# quanton_rev_1.net
KiCad netlist of a schematic drawn in EAGLE
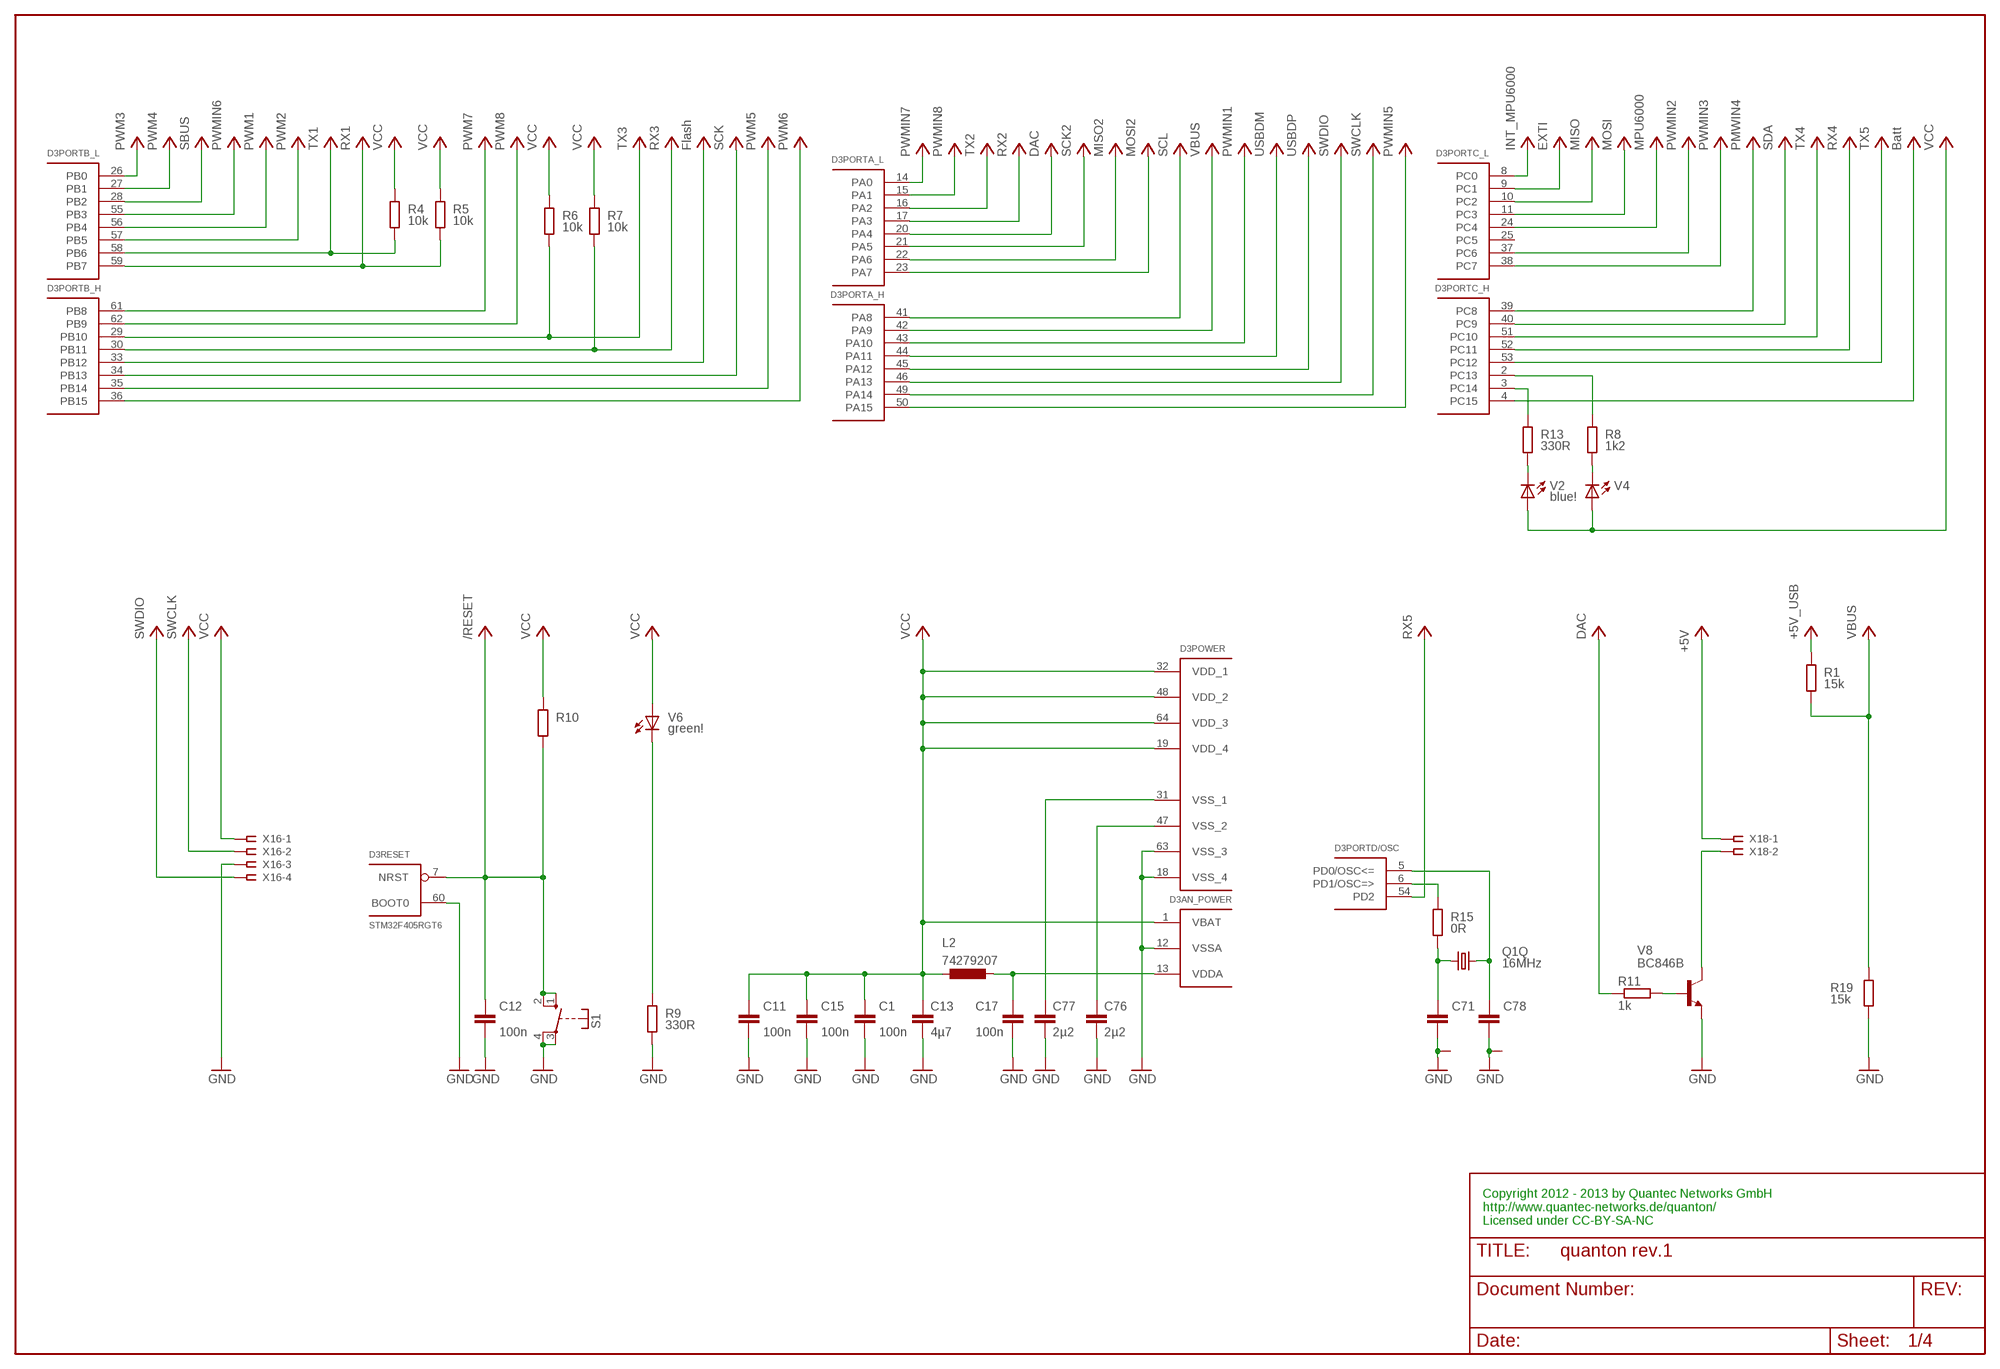
[diagram p0: schematic, sheet 1]
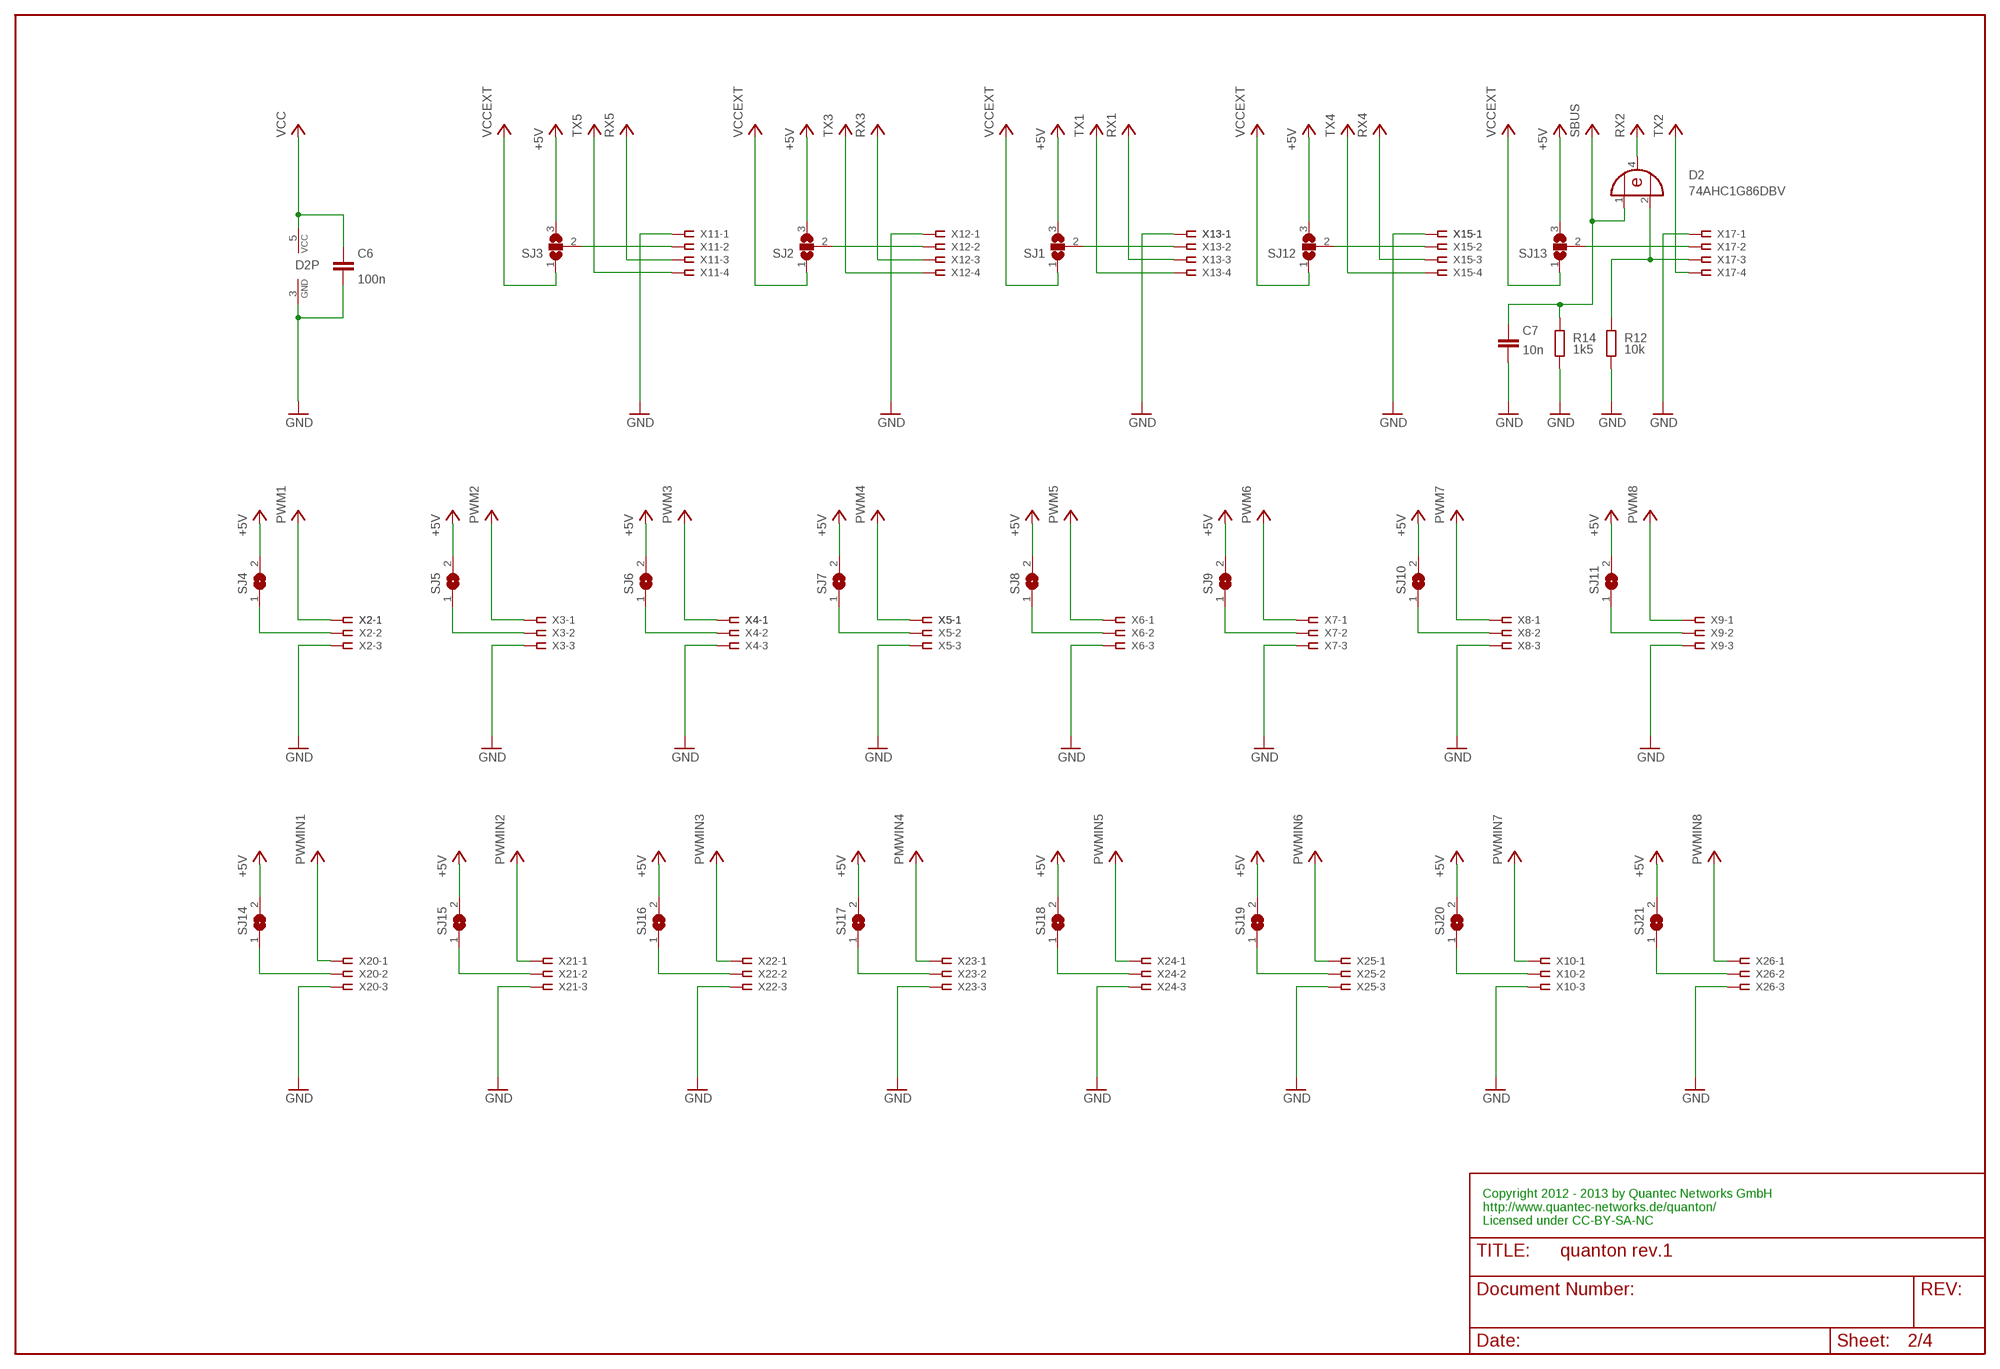
[diagram p1: schematic, sheet 2]
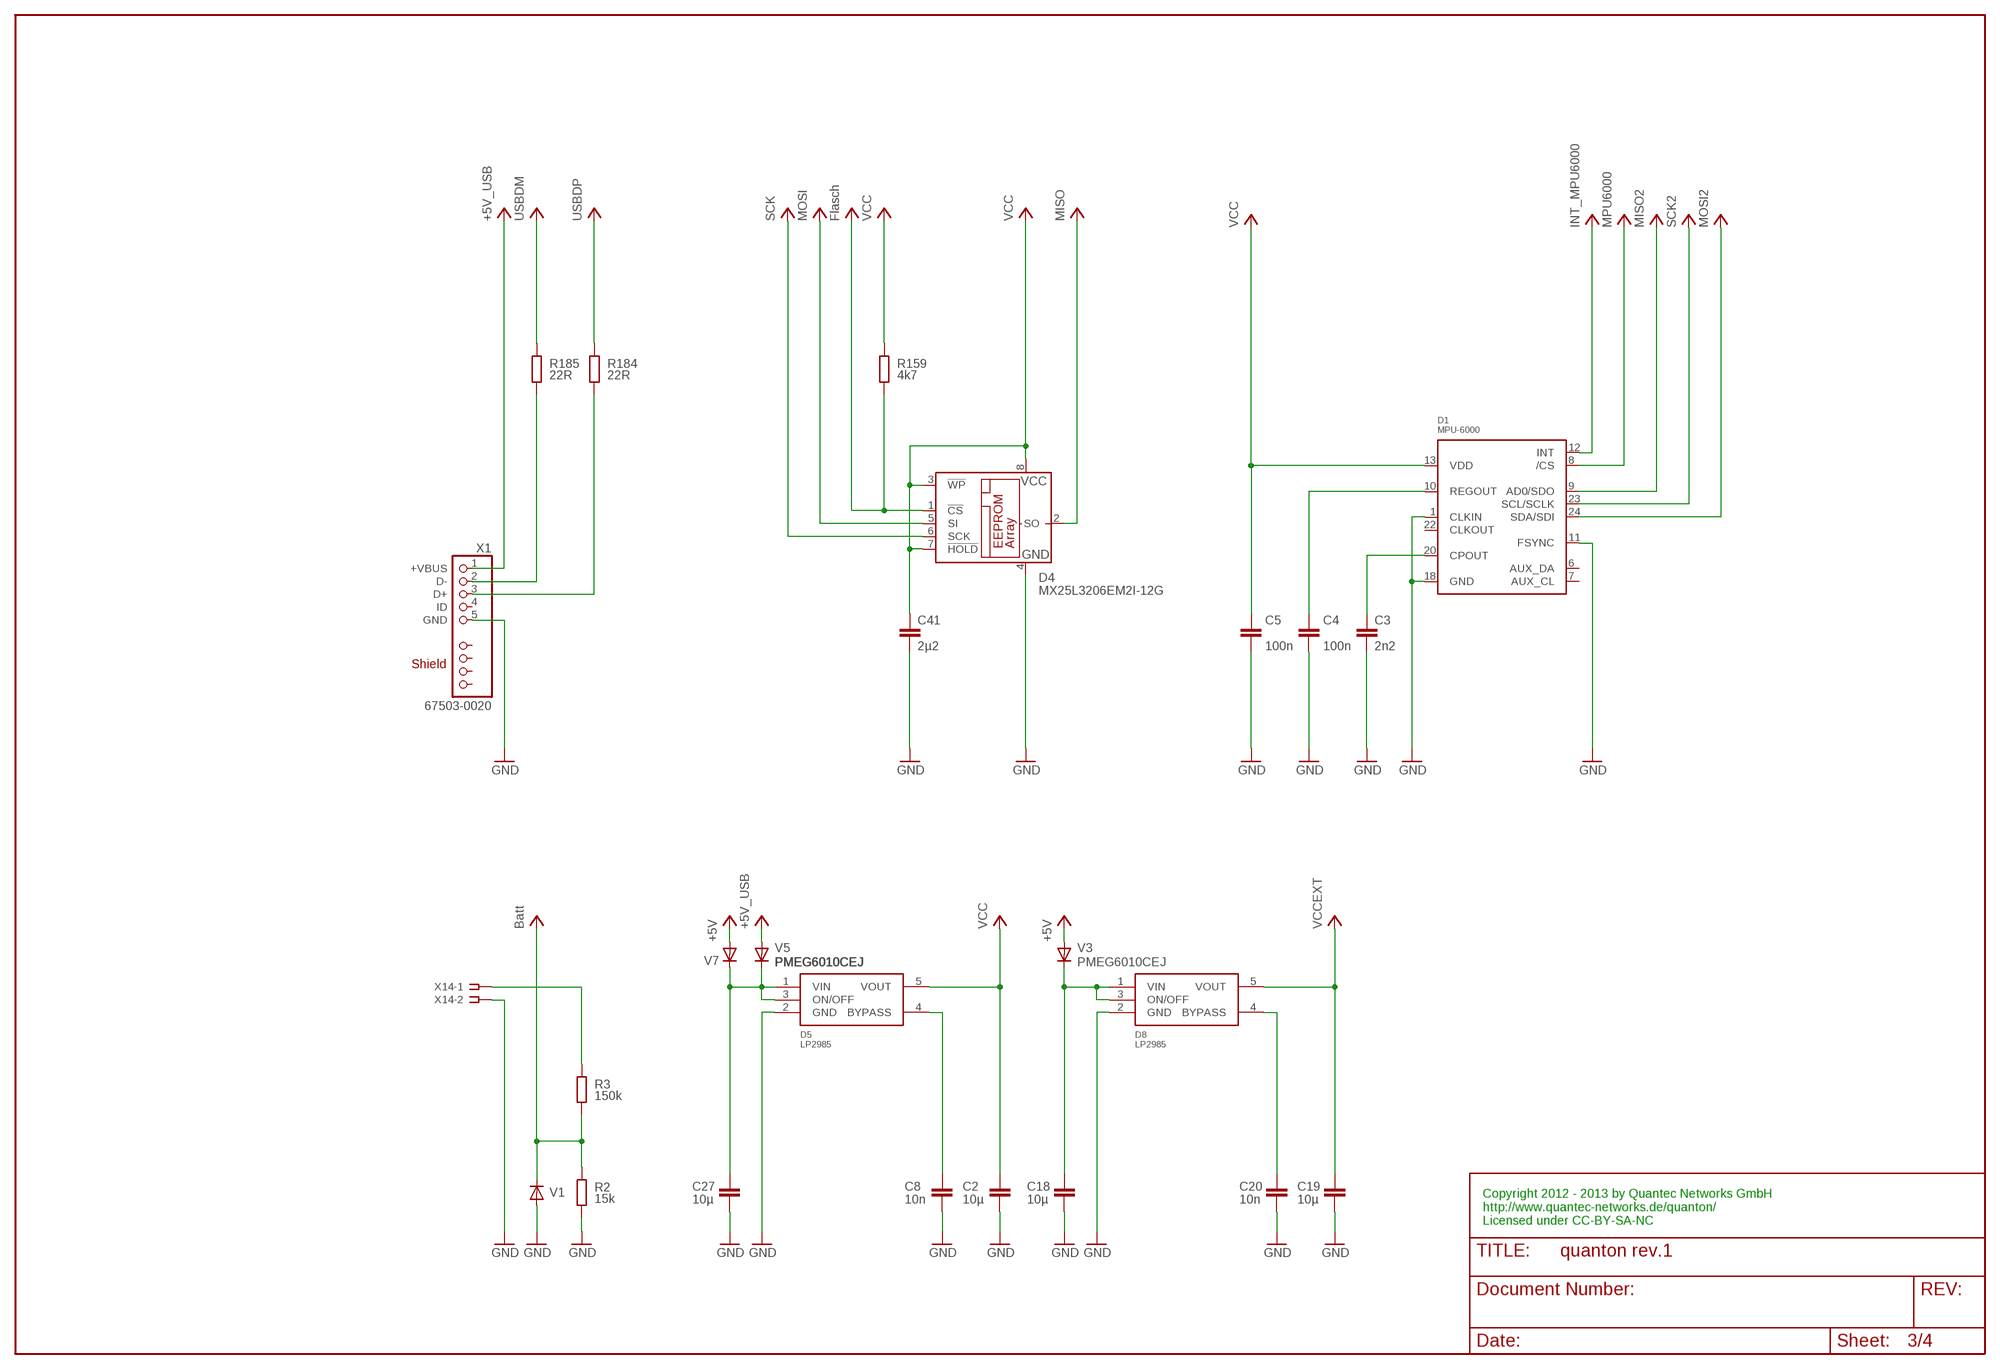
[diagram p2: schematic, sheet 3]
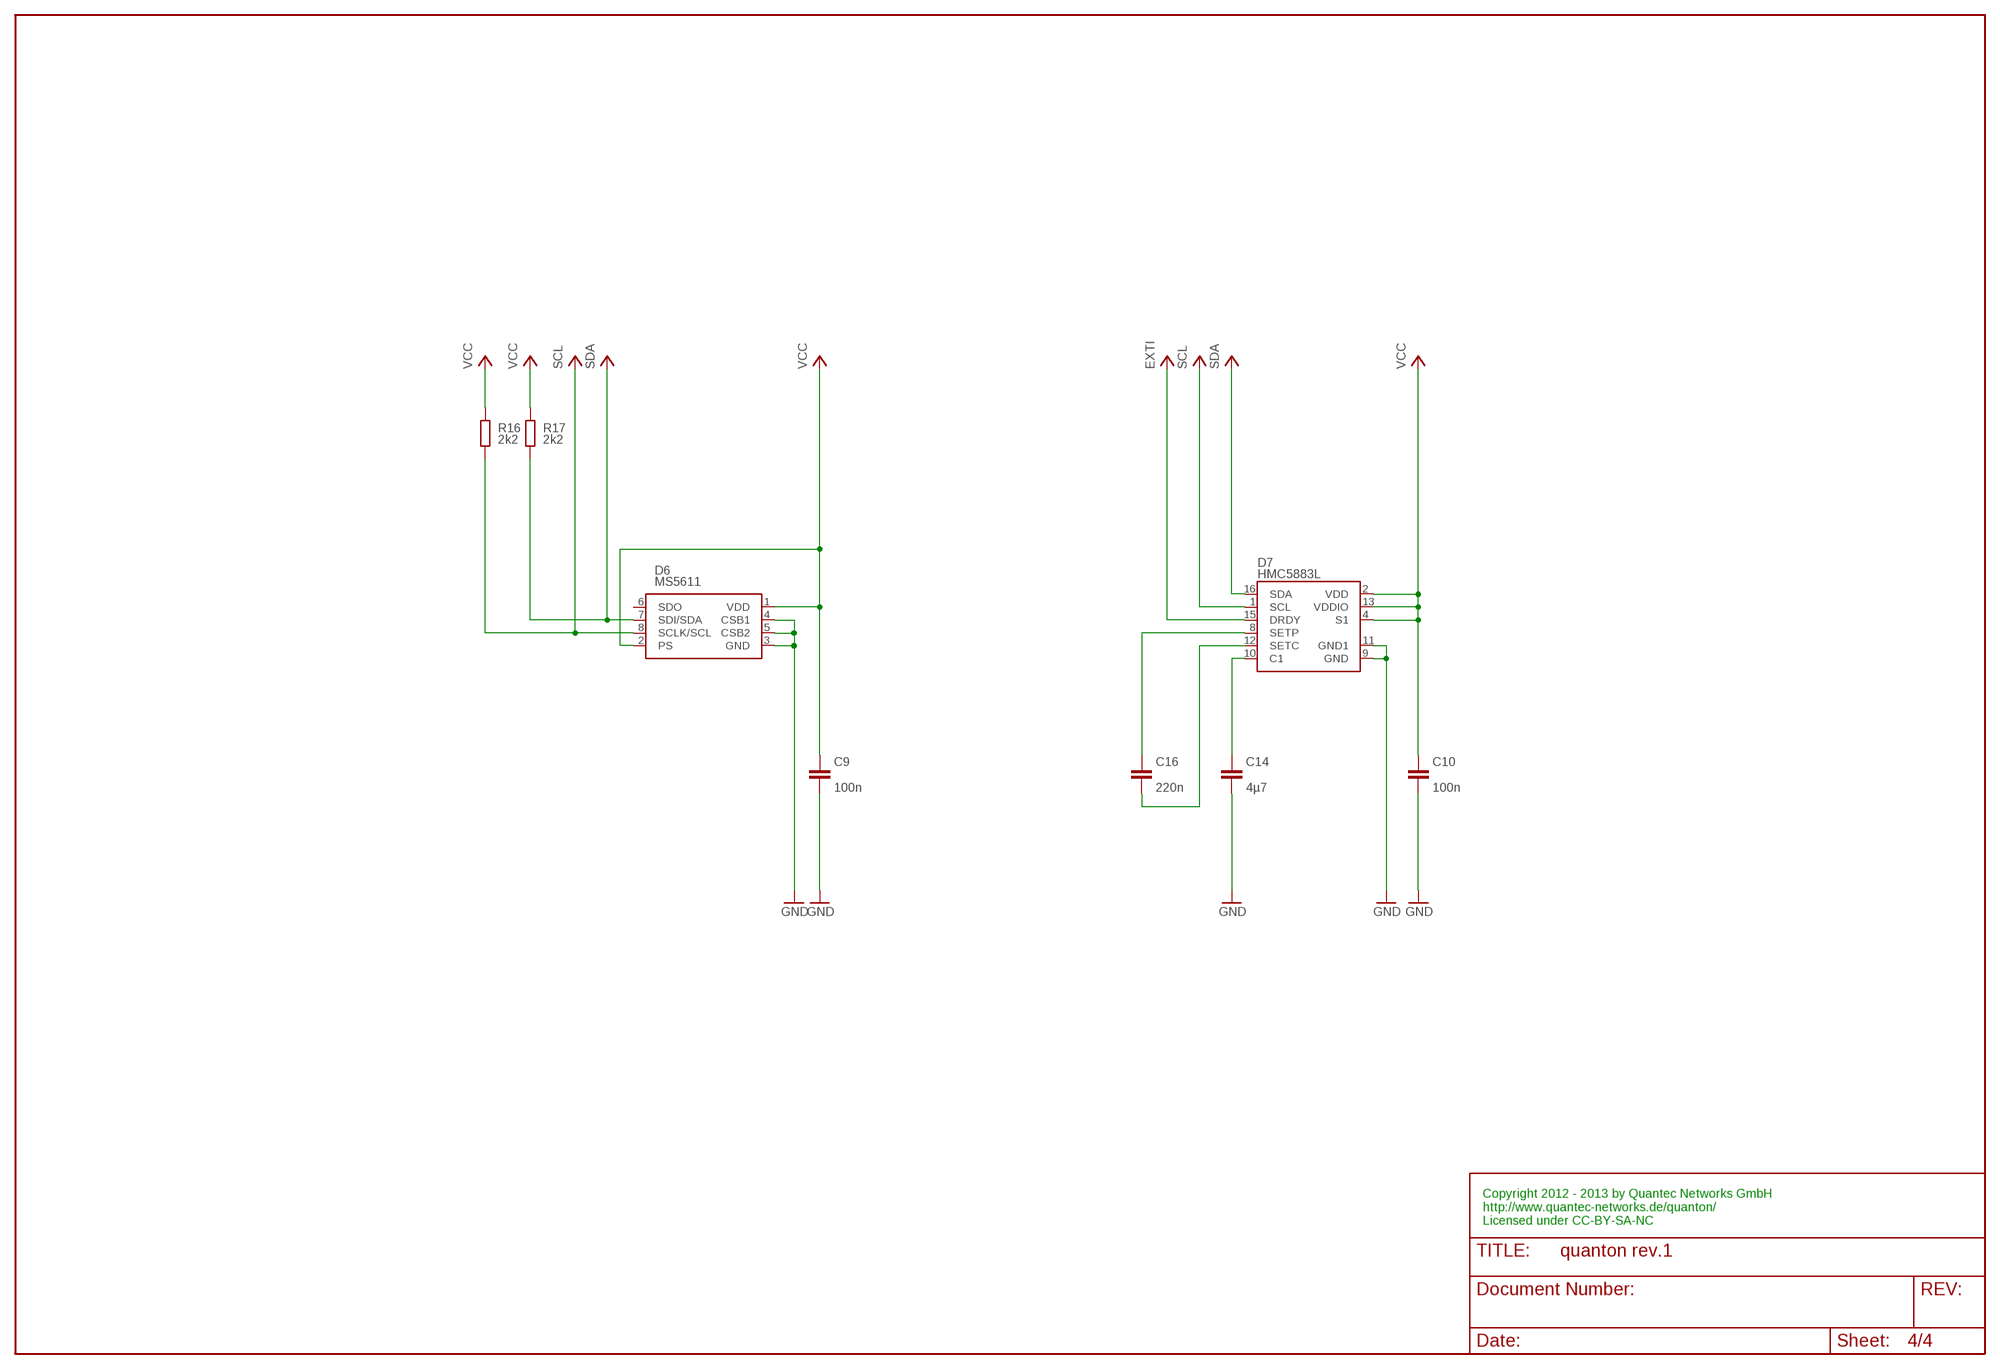
[diagram p3: schematic, sheet 4]

(export (version "E")
  (design (tool "Eeschema 10.0.6"))
  (components
    (comp (ref "C9")
      (value "100n")
      (footprint "eagle-import:C0402")
      (libsource (lib "eagle-import") (part "C-EUC0402"))
    )
    (comp (ref "C10")
      (value "100n")
      (footprint "eagle-import:C0402")
      (libsource (lib "eagle-import") (part "C-EUC0402"))
    )
    (comp (ref "C14")
      (value "4µ7")
      (footprint "eagle-import:C0805")
      (libsource (lib "eagle-import") (part "C-EUC0805"))
    )
    (comp (ref "C16")
      (value "220n")
      (footprint "eagle-import:C0603")
      (libsource (lib "eagle-import") (part "C-EUC0603"))
    )
    (comp (ref "D6")
      (value "MS5611")
      (footprint "eagle-import:QFN8-5X3")
      (libsource (lib "eagle-import") (part "MS5611"))
    )
    (comp (ref "D7")
      (value "HMC5883L")
      (footprint "eagle-import:LCC16-3X3")
      (libsource (lib "eagle-import") (part "HMC5883L"))
    )
    (comp (ref "R16")
      (value "2k2")
      (footprint "eagle-import:R0603")
      (libsource (lib "eagle-import") (part "R-EU_R0603"))
    )
    (comp (ref "R17")
      (value "2k2")
      (footprint "eagle-import:R0603")
      (libsource (lib "eagle-import") (part "R-EU_R0603"))
    )
    (comp (ref "C6")
      (value "100n")
      (footprint "eagle-import:C0402")
      (libsource (lib "eagle-import") (part "C-EUC0402"))
    )
    (comp (ref "C7")
      (value "10n")
      (footprint "eagle-import:C0603")
      (libsource (lib "eagle-import") (part "C-EUC0603"))
    )
    (comp (ref "D2")
      (value "74AHC1G86DBV")
      (footprint "eagle-import:SOT23-5")
      (fields (field (name "ABAS") "12532"))
      (libsource (lib "eagle-import") (part "741G86DBVAHC"))
    )
    (comp (ref "R12")
      (value "10k")
      (footprint "eagle-import:R0603")
      (libsource (lib "eagle-import") (part "R-EU_R0603"))
    )
    (comp (ref "R14")
      (value "1k5")
      (footprint "eagle-import:R0603")
      (libsource (lib "eagle-import") (part "R-EU_R0603"))
    )
    (comp (ref "SJ1")
      (value "SJ2W")
      (footprint "eagle-import:SJ_2")
      (libsource (lib "eagle-import") (part "SJ2W"))
    )
    (comp (ref "SJ2")
      (value "SJ2W")
      (footprint "eagle-import:SJ_2")
      (libsource (lib "eagle-import") (part "SJ2W"))
    )
    (comp (ref "SJ3")
      (value "SJ2W")
      (footprint "eagle-import:SJ_2")
      (libsource (lib "eagle-import") (part "SJ2W"))
    )
    (comp (ref "SJ4") (value "SJ") (footprint "eagle-import:SJ") (libsource (lib "eagle-import") (part "SJ")))
    (comp (ref "SJ5") (value "SJ") (footprint "eagle-import:SJ") (libsource (lib "eagle-import") (part "SJ")))
    (comp (ref "SJ6") (value "SJ") (footprint "eagle-import:SJ") (libsource (lib "eagle-import") (part "SJ")))
    (comp (ref "SJ7") (value "SJ") (footprint "eagle-import:SJ") (libsource (lib "eagle-import") (part "SJ")))
    (comp (ref "SJ8") (value "SJ") (footprint "eagle-import:SJ") (libsource (lib "eagle-import") (part "SJ")))
    (comp (ref "SJ9") (value "SJ") (footprint "eagle-import:SJ") (libsource (lib "eagle-import") (part "SJ")))
    (comp (ref "SJ10")
      (value "SJ")
      (footprint "eagle-import:SJ")
      (libsource (lib "eagle-import") (part "SJ"))
    )
    (comp (ref "SJ11")
      (value "SJ")
      (footprint "eagle-import:SJ")
      (libsource (lib "eagle-import") (part "SJ"))
    )
    (comp (ref "SJ12")
      (value "SJ2W")
      (footprint "eagle-import:SJ_2")
      (libsource (lib "eagle-import") (part "SJ2W"))
    )
    (comp (ref "SJ13")
      (value "SJ2W")
      (footprint "eagle-import:SJ_2")
      (libsource (lib "eagle-import") (part "SJ2W"))
    )
    (comp (ref "SJ14")
      (value "SJ")
      (footprint "eagle-import:SJ")
      (libsource (lib "eagle-import") (part "SJ"))
    )
    (comp (ref "SJ15")
      (value "SJ")
      (footprint "eagle-import:SJ")
      (libsource (lib "eagle-import") (part "SJ"))
    )
    (comp (ref "SJ16")
      (value "SJ")
      (footprint "eagle-import:SJ")
      (libsource (lib "eagle-import") (part "SJ"))
    )
    (comp (ref "SJ17")
      (value "SJ")
      (footprint "eagle-import:SJ")
      (libsource (lib "eagle-import") (part "SJ"))
    )
    (comp (ref "SJ18")
      (value "SJ")
      (footprint "eagle-import:SJ")
      (libsource (lib "eagle-import") (part "SJ"))
    )
    (comp (ref "SJ19")
      (value "SJ")
      (footprint "eagle-import:SJ")
      (libsource (lib "eagle-import") (part "SJ"))
    )
    (comp (ref "SJ20")
      (value "SJ")
      (footprint "eagle-import:SJ")
      (libsource (lib "eagle-import") (part "SJ"))
    )
    (comp (ref "SJ21")
      (value "SJ")
      (footprint "eagle-import:SJ")
      (libsource (lib "eagle-import") (part "SJ"))
    )
    (comp (ref "X2")
      (value "SSW-101-02-S-T")
      (footprint "eagle-import:SSW-101-02-S-T")
      (fields (field (name "ABAS") "-1"))
      (libsource (lib "eagle-import") (part "SSW-101-02-S-T"))
    )
    (comp (ref "X3")
      (value "SSW-101-02-S-T")
      (footprint "eagle-import:SSW-101-02-S-T")
      (fields
        (field (name "ABAS") "-1")
        (field (name "MPN") "SSW-101-02-S-T")
        (field (name "OC_FARNELL") "unknown")
        (field (name "OC_NEWARK") "82P1460")
      )
      (libsource (lib "eagle-import") (part "SSW-101-02-S-T"))
    )
    (comp (ref "X4")
      (value "SSW-101-02-S-T")
      (footprint "eagle-import:SSW-101-02-S-T")
      (fields
        (field (name "ABAS") "-1")
        (field (name "MPN") "SSW-101-02-S-T")
        (field (name "OC_FARNELL") "unknown")
        (field (name "OC_NEWARK") "82P1460")
      )
      (libsource (lib "eagle-import") (part "SSW-101-02-S-T"))
    )
    (comp (ref "X5")
      (value "SSW-101-02-S-T")
      (footprint "eagle-import:SSW-101-02-S-T")
      (fields
        (field (name "ABAS") "-1")
        (field (name "MPN") "SSW-101-02-S-T")
        (field (name "OC_FARNELL") "unknown")
        (field (name "OC_NEWARK") "82P1460")
      )
      (libsource (lib "eagle-import") (part "SSW-101-02-S-T"))
    )
    (comp (ref "X6")
      (value "SSW-101-02-S-T")
      (footprint "eagle-import:SSW-101-02-S-T")
      (fields
        (field (name "ABAS") "-1")
        (field (name "MPN") "SSW-101-02-S-T")
        (field (name "OC_FARNELL") "unknown")
        (field (name "OC_NEWARK") "82P1460")
      )
      (libsource (lib "eagle-import") (part "SSW-101-02-S-T"))
    )
    (comp (ref "X7")
      (value "SSW-101-02-S-T")
      (footprint "eagle-import:SSW-101-02-S-T")
      (fields
        (field (name "ABAS") "-1")
        (field (name "MPN") "SSW-101-02-S-T")
        (field (name "OC_FARNELL") "unknown")
        (field (name "OC_NEWARK") "82P1460")
      )
      (libsource (lib "eagle-import") (part "SSW-101-02-S-T"))
    )
    (comp (ref "X8")
      (value "SSW-101-02-S-T")
      (footprint "eagle-import:SSW-101-02-S-T")
      (fields
        (field (name "ABAS") "-1")
        (field (name "MPN") "SSW-101-02-S-T")
        (field (name "OC_FARNELL") "unknown")
        (field (name "OC_NEWARK") "82P1460")
      )
      (libsource (lib "eagle-import") (part "SSW-101-02-S-T"))
    )
    (comp (ref "X9")
      (value "SSW-101-02-S-T")
      (footprint "eagle-import:SSW-101-02-S-T")
      (fields
        (field (name "ABAS") "-1")
        (field (name "MPN") "SSW-101-02-S-T")
        (field (name "OC_FARNELL") "unknown")
        (field (name "OC_NEWARK") "82P1460")
      )
      (libsource (lib "eagle-import") (part "SSW-101-02-S-T"))
    )
    (comp (ref "X10")
      (value "SSW-101-02-S-T")
      (footprint "eagle-import:SSW-101-02-S-T")
      (fields
        (field (name "ABAS") "-1")
        (field (name "MPN") "SSW-101-02-S-T")
        (field (name "OC_FARNELL") "unknown")
        (field (name "OC_NEWARK") "82P1460")
      )
      (libsource (lib "eagle-import") (part "SSW-101-02-S-T"))
    )
    (comp (ref "X11")
      (value "SSW-104-02-S-S")
      (footprint "eagle-import:SSW-104-02-S-S")
      (fields (field (name "ABAS") "-1"))
      (libsource (lib "eagle-import") (part "SSW-104-02-S-S"))
    )
    (comp (ref "X12")
      (value "SSW-104-02-S-S")
      (footprint "eagle-import:SSW-104-02-S-S")
      (fields (field (name "ABAS") "-1"))
      (libsource (lib "eagle-import") (part "SSW-104-02-S-S"))
    )
    (comp (ref "X13")
      (value "SSW-104-02-S-S")
      (footprint "eagle-import:SSW-104-02-S-S")
      (fields (field (name "ABAS") "-1"))
      (libsource (lib "eagle-import") (part "SSW-104-02-S-S"))
    )
    (comp (ref "X15")
      (value "SSW-104-02-S-S")
      (footprint "eagle-import:SSW-104-02-S-S")
      (fields (field (name "ABAS") "-1"))
      (libsource (lib "eagle-import") (part "SSW-104-02-S-S"))
    )
    (comp (ref "X17")
      (value "SSW-104-02-S-S")
      (footprint "eagle-import:SSW-104-02-S-S")
      (fields (field (name "ABAS") "-1"))
      (libsource (lib "eagle-import") (part "SSW-104-02-S-S"))
    )
    (comp (ref "X20")
      (value "SSW-101-02-S-T")
      (footprint "eagle-import:SSW-101-02-S-T")
      (fields
        (field (name "ABAS") "-1")
        (field (name "MPN") "SSW-101-02-S-T")
        (field (name "OC_FARNELL") "unknown")
        (field (name "OC_NEWARK") "82P1460")
      )
      (libsource (lib "eagle-import") (part "SSW-101-02-S-T"))
    )
    (comp (ref "X21")
      (value "SSW-101-02-S-T")
      (footprint "eagle-import:SSW-101-02-S-T")
      (fields
        (field (name "ABAS") "-1")
        (field (name "MPN") "SSW-101-02-S-T")
        (field (name "OC_FARNELL") "unknown")
        (field (name "OC_NEWARK") "82P1460")
      )
      (libsource (lib "eagle-import") (part "SSW-101-02-S-T"))
    )
    (comp (ref "X22")
      (value "SSW-101-02-S-T")
      (footprint "eagle-import:SSW-101-02-S-T")
      (fields
        (field (name "ABAS") "-1")
        (field (name "MPN") "SSW-101-02-S-T")
        (field (name "OC_FARNELL") "unknown")
        (field (name "OC_NEWARK") "82P1460")
      )
      (libsource (lib "eagle-import") (part "SSW-101-02-S-T"))
    )
    (comp (ref "X23")
      (value "SSW-101-02-S-T")
      (footprint "eagle-import:SSW-101-02-S-T")
      (fields
        (field (name "ABAS") "-1")
        (field (name "MPN") "SSW-101-02-S-T")
        (field (name "OC_FARNELL") "unknown")
        (field (name "OC_NEWARK") "82P1460")
      )
      (libsource (lib "eagle-import") (part "SSW-101-02-S-T"))
    )
    (comp (ref "X24")
      (value "SSW-101-02-S-T")
      (footprint "eagle-import:SSW-101-02-S-T")
      (fields
        (field (name "ABAS") "-1")
        (field (name "MPN") "SSW-101-02-S-T")
        (field (name "OC_FARNELL") "unknown")
        (field (name "OC_NEWARK") "82P1460")
      )
      (libsource (lib "eagle-import") (part "SSW-101-02-S-T"))
    )
    (comp (ref "X25")
      (value "SSW-101-02-S-T")
      (footprint "eagle-import:SSW-101-02-S-T")
      (fields
        (field (name "MPN") "SSW-101-02-S-T")
        (field (name "OC_FARNELL") "unknown")
        (field (name "OC_NEWARK") "82P1460")
        (field (name "ABAS") "-1")
      )
      (libsource (lib "eagle-import") (part "SSW-101-02-S-T"))
    )
    (comp (ref "X26")
      (value "SSW-101-02-S-T")
      (footprint "eagle-import:SSW-101-02-S-T")
      (fields
        (field (name "MPN") "SSW-101-02-S-T")
        (field (name "OC_FARNELL") "unknown")
        (field (name "OC_NEWARK") "82P1460")
        (field (name "ABAS") "-1")
      )
      (libsource (lib "eagle-import") (part "SSW-101-02-S-T"))
    )
    (comp (ref "C2")
      (value "10µ")
      (footprint "eagle-import:C0805")
      (libsource (lib "eagle-import") (part "C-EUC0805"))
    )
    (comp (ref "C3")
      (value "2n2")
      (footprint "eagle-import:C0603")
      (libsource (lib "eagle-import") (part "C-EUC0603"))
    )
    (comp (ref "C4")
      (value "100n")
      (footprint "eagle-import:C0402")
      (libsource (lib "eagle-import") (part "C-EUC0402"))
    )
    (comp (ref "C5")
      (value "100n")
      (footprint "eagle-import:C0402")
      (libsource (lib "eagle-import") (part "C-EUC0402"))
    )
    (comp (ref "C8")
      (value "10n")
      (footprint "eagle-import:C0603")
      (libsource (lib "eagle-import") (part "C-EUC0603"))
    )
    (comp (ref "C18")
      (value "10µ")
      (footprint "eagle-import:C0805")
      (libsource (lib "eagle-import") (part "C-EUC0805"))
    )
    (comp (ref "C19")
      (value "10µ")
      (footprint "eagle-import:C0805")
      (libsource (lib "eagle-import") (part "C-EUC0805"))
    )
    (comp (ref "C20")
      (value "10n")
      (footprint "eagle-import:C0603")
      (libsource (lib "eagle-import") (part "C-EUC0603"))
    )
    (comp (ref "C27")
      (value "10µ")
      (footprint "eagle-import:C0805")
      (libsource (lib "eagle-import") (part "C-EUC0805"))
    )
    (comp (ref "C41")
      (value "2µ2")
      (footprint "eagle-import:C0603")
      (libsource (lib "eagle-import") (part "C-EUC0603"))
    )
    (comp (ref "D1")
      (value "MPU-6000")
      (footprint "eagle-import:QFN24-4X4")
      (libsource (lib "eagle-import") (part "MPU-6000"))
    )
    (comp (ref "D4")
      (value "MX25L3206EM2I-12G")
      (footprint "eagle-import:SOIC8")
      (libsource (lib "eagle-import") (part "AT26DF081A-SU"))
    )
    (comp (ref "D5")
      (value "LP2985")
      (footprint "eagle-import:SOT23-5")
      (libsource (lib "eagle-import") (part "LP2985"))
    )
    (comp (ref "D8")
      (value "LP2985")
      (footprint "eagle-import:SOT23-5")
      (libsource (lib "eagle-import") (part "LP2985"))
    )
    (comp (ref "R2")
      (value "15k")
      (footprint "eagle-import:R0603")
      (libsource (lib "eagle-import") (part "R-EU_R0603"))
    )
    (comp (ref "R3")
      (value "150k")
      (footprint "eagle-import:R0603")
      (libsource (lib "eagle-import") (part "R-EU_R0603"))
    )
    (comp (ref "R159")
      (value "4k7")
      (footprint "eagle-import:R0603")
      (libsource (lib "eagle-import") (part "R-EU_R0603"))
    )
    (comp (ref "R184")
      (value "22R")
      (footprint "eagle-import:R0402")
      (libsource (lib "eagle-import") (part "R-EU_R0402"))
    )
    (comp (ref "R185")
      (value "22R")
      (footprint "eagle-import:R0402")
      (libsource (lib "eagle-import") (part "R-EU_R0402"))
    )
    (comp (ref "V1")
      (value "PMEG6010CEJ")
      (footprint "eagle-import:SOD323-R")
      (libsource (lib "eagle-import") (part "DIODE-SOD323-R"))
    )
    (comp (ref "V3")
      (value "PMEG6010CEJ")
      (footprint "eagle-import:SOD323-R")
      (libsource (lib "eagle-import") (part "DIODE-SOD323-R"))
    )
    (comp (ref "V5")
      (value "PMEG6010CEJ")
      (footprint "eagle-import:SOD323-R")
      (libsource (lib "eagle-import") (part "DIODE-SOD323-R"))
    )
    (comp (ref "V7")
      (value "PMEG6010CEJ")
      (footprint "eagle-import:SOD323-R")
      (libsource (lib "eagle-import") (part "DIODE-SOD323-R"))
    )
    (comp (ref "X1")
      (value "67503-0020")
      (footprint "eagle-import:67503-0020")
      (libsource (lib "eagle-import") (part "67503-0020"))
    )
    (comp (ref "X14")
      (value "SSW-101-02-S-D")
      (footprint "eagle-import:SSW-101-02-S-D")
      (fields (field (name "ABAS") "-1"))
      (libsource (lib "eagle-import") (part "SSW-101-02-S-D"))
    )
    (comp (ref "C1")
      (value "100n")
      (footprint "eagle-import:C0402")
      (libsource (lib "eagle-import") (part "C-EUC0402"))
    )
    (comp (ref "C11")
      (value "100n")
      (footprint "eagle-import:C0402")
      (libsource (lib "eagle-import") (part "C-EUC0402"))
    )
    (comp (ref "C12")
      (value "100n")
      (footprint "eagle-import:C0402")
      (libsource (lib "eagle-import") (part "C-EUC0402"))
    )
    (comp (ref "C13")
      (value "4µ7")
      (footprint "eagle-import:C0805")
      (libsource (lib "eagle-import") (part "C-EUC0805"))
    )
    (comp (ref "C15")
      (value "100n")
      (footprint "eagle-import:C0402")
      (libsource (lib "eagle-import") (part "C-EUC0402"))
    )
    (comp (ref "C17")
      (value "100n")
      (footprint "eagle-import:C0402")
      (libsource (lib "eagle-import") (part "C-EUC0402"))
    )
    (comp (ref "C71")
      (value "C-EUC0603")
      (footprint "eagle-import:C0603")
      (libsource (lib "eagle-import") (part "C-EUC0603"))
    )
    (comp (ref "C76")
      (value "2µ2")
      (footprint "eagle-import:C0603")
      (libsource (lib "eagle-import") (part "C-EUC0603"))
    )
    (comp (ref "C77")
      (value "2µ2")
      (footprint "eagle-import:C0603")
      (libsource (lib "eagle-import") (part "C-EUC0603"))
    )
    (comp (ref "C78")
      (value "C-EUC0603")
      (footprint "eagle-import:C0603")
      (libsource (lib "eagle-import") (part "C-EUC0603"))
    )
    (comp (ref "D3")
      (value "STM32F405RGT6")
      (footprint "eagle-import:TQFP64")
      (fields (field (name "ABAS") "12531"))
      (libsource (lib "eagle-import") (part "STM32F10XRXT6"))
    )
    (comp (ref "L2")
      (value "74279207")
      (footprint "eagle-import:R0805")
      (libsource (lib "eagle-import") (part "L-EU0805"))
    )
    (comp (ref "Q1")
      (value "16MHz")
      (footprint "eagle-import:50X32")
      (fields (field (name "ABAS") "12620"))
      (libsource (lib "eagle-import") (part "50X32"))
    )
    (comp (ref "R1")
      (value "15k")
      (footprint "eagle-import:R0603")
      (libsource (lib "eagle-import") (part "R-EU_R0603"))
    )
    (comp (ref "R4")
      (value "10k")
      (footprint "eagle-import:R0603")
      (libsource (lib "eagle-import") (part "R-EU_R0603"))
    )
    (comp (ref "R5")
      (value "10k")
      (footprint "eagle-import:R0603")
      (libsource (lib "eagle-import") (part "R-EU_R0603"))
    )
    (comp (ref "R6")
      (value "10k")
      (footprint "eagle-import:R0603")
      (libsource (lib "eagle-import") (part "R-EU_R0603"))
    )
    (comp (ref "R7")
      (value "10k")
      (footprint "eagle-import:R0603")
      (libsource (lib "eagle-import") (part "R-EU_R0603"))
    )
    (comp (ref "R8")
      (value "1k2")
      (footprint "eagle-import:R0603")
      (libsource (lib "eagle-import") (part "R-EU_R0603"))
    )
    (comp (ref "R9")
      (value "330R")
      (footprint "eagle-import:R0603")
      (libsource (lib "eagle-import") (part "R-EU_R0603"))
    )
    (comp (ref "R10")
      (value "R-EU_R0603")
      (footprint "eagle-import:R0603")
      (libsource (lib "eagle-import") (part "R-EU_R0603"))
    )
    (comp (ref "R11")
      (value "1k")
      (footprint "eagle-import:R0603")
      (libsource (lib "eagle-import") (part "R-EU_R0603"))
    )
    (comp (ref "R13")
      (value "330R")
      (footprint "eagle-import:R0603")
      (libsource (lib "eagle-import") (part "R-EU_R0603"))
    )
    (comp (ref "R15")
      (value "0R")
      (footprint "eagle-import:R0603")
      (libsource (lib "eagle-import") (part "R-EU_R0603"))
    )
    (comp (ref "R19")
      (value "15k")
      (footprint "eagle-import:R0603")
      (libsource (lib "eagle-import") (part "R-EU_R0603"))
    )
    (comp (ref "S1")
      (value "KSCXXXX")
      (footprint "eagle-import:KSCXXXJ")
      (libsource (lib "eagle-import") (part "KSCXXXX"))
    )
    (comp (ref "V2")
      (value "blue!")
      (footprint "eagle-import:CHIP-LED0805")
      (libsource (lib "eagle-import") (part "LEDCHIP-LED0805"))
    )
    (comp (ref "V4")
      (value "red!")
      (footprint "eagle-import:CHIP-LED0805")
      (libsource (lib "eagle-import") (part "LEDCHIP-LED0805"))
    )
    (comp (ref "V6")
      (value "green!")
      (footprint "eagle-import:CHIP-LED0805")
      (libsource (lib "eagle-import") (part "LEDCHIP-LED0805"))
    )
    (comp (ref "V8")
      (value "BC846B")
      (footprint "eagle-import:SOT23")
      (libsource (lib "eagle-import") (part "BC846SMDB"))
    )
    (comp (ref "X16")
      (value "SSW-104-02-S-S")
      (footprint "eagle-import:SSW-104-02-S-S")
      (fields (field (name "ABAS") "-1"))
      (libsource (lib "eagle-import") (part "SSW-104-02-S-S"))
    )
    (comp (ref "X18")
      (value "SSW-101-02-S-D")
      (footprint "eagle-import:SSW-101-02-S-D")
      (fields (field (name "ABAS") "-1"))
      (libsource (lib "eagle-import") (part "SSW-101-02-S-D"))
    )
  )
  (nets
    (net (code "1") (name "+5V") (class "Default")
      (node (ref "SJ1") (pin "3") (pinfunction "3_3") (pintype "passive"))
      (node (ref "SJ10") (pin "2") (pinfunction "2_2") (pintype "passive"))
      (node (ref "SJ11") (pin "2") (pinfunction "2_2") (pintype "passive"))
      (node (ref "SJ12") (pin "3") (pinfunction "3_3") (pintype "passive"))
      (node (ref "SJ13") (pin "3") (pinfunction "3_3") (pintype "passive"))
      (node (ref "SJ14") (pin "2") (pinfunction "2_2") (pintype "passive"))
      (node (ref "SJ15") (pin "2") (pinfunction "2_2") (pintype "passive"))
      (node (ref "SJ16") (pin "2") (pinfunction "2_2") (pintype "passive"))
      (node (ref "SJ17") (pin "2") (pinfunction "2_2") (pintype "passive"))
      (node (ref "SJ18") (pin "2") (pinfunction "2_2") (pintype "passive"))
      (node (ref "SJ19") (pin "2") (pinfunction "2_2") (pintype "passive"))
      (node (ref "SJ2") (pin "3") (pinfunction "3_3") (pintype "passive"))
      (node (ref "SJ20") (pin "2") (pinfunction "2_2") (pintype "passive"))
      (node (ref "SJ21") (pin "2") (pinfunction "2_2") (pintype "passive"))
      (node (ref "SJ3") (pin "3") (pinfunction "3_3") (pintype "passive"))
      (node (ref "SJ4") (pin "2") (pinfunction "2_2") (pintype "passive"))
      (node (ref "SJ5") (pin "2") (pinfunction "2_2") (pintype "passive"))
      (node (ref "SJ6") (pin "2") (pinfunction "2_2") (pintype "passive"))
      (node (ref "SJ7") (pin "2") (pinfunction "2_2") (pintype "passive"))
      (node (ref "SJ8") (pin "2") (pinfunction "2_2") (pintype "passive"))
      (node (ref "SJ9") (pin "2") (pinfunction "2_2") (pintype "passive"))
      (node (ref "V3") (pin "A") (pinfunction "A_A") (pintype "passive"))
      (node (ref "V7") (pin "A") (pinfunction "A_A") (pintype "passive"))
      (node (ref "X18") (pin "1") (pinfunction "1_1") (pintype "passive"))
    )
    (net (code "2") (name "+5V_USB") (class "Default")
      (node (ref "R1") (pin "2") (pinfunction "2_2") (pintype "passive"))
      (node (ref "V5") (pin "A") (pinfunction "A_A") (pintype "passive"))
      (node (ref "X1") (pin "1") (pinfunction "+VBUS_1") (pintype "passive"))
    )
    (net (code "3") (name "BATT") (class "Default")
      (node (ref "D3") (pin "4") (pinfunction "PC15_4") (pintype "bidirectional"))
      (node (ref "R2") (pin "2") (pinfunction "2_2") (pintype "passive"))
      (node (ref "R3") (pin "1") (pinfunction "1_1") (pintype "passive"))
      (node (ref "V1") (pin "C") (pinfunction "C_C") (pintype "passive"))
    )
    (net (code "4") (name "DAC") (class "Default")
      (node (ref "D3") (pin "20") (pinfunction "PA4_20") (pintype "bidirectional"))
      (node (ref "R11") (pin "1") (pinfunction "1_1") (pintype "passive"))
    )
    (net (code "5") (name "EXTI") (class "Default")
      (node (ref "D3") (pin "9") (pinfunction "PC1_9") (pintype "bidirectional"))
      (node (ref "D7") (pin "15") (pinfunction "DRDY_15") (pintype "bidirectional"))
    )
    (net (code "6") (name "FLASH") (class "Default")
      (node (ref "D3") (pin "33") (pinfunction "PB12_33") (pintype "bidirectional"))
      (node (ref "D4") (pin "1") (pinfunction "~{CS}_1") (pintype "input"))
      (node (ref "R159") (pin "1") (pinfunction "1_1") (pintype "passive"))
    )
    (net (code "7") (name "GND") (class "Default")
      (node (ref "C1") (pin "2") (pinfunction "2_2") (pintype "passive"))
      (node (ref "C10") (pin "2") (pinfunction "2_2") (pintype "passive"))
      (node (ref "C11") (pin "2") (pinfunction "2_2") (pintype "passive"))
      (node (ref "C12") (pin "2") (pinfunction "2_2") (pintype "passive"))
      (node (ref "C13") (pin "2") (pinfunction "2_2") (pintype "passive"))
      (node (ref "C14") (pin "2") (pinfunction "2_2") (pintype "passive"))
      (node (ref "C15") (pin "2") (pinfunction "2_2") (pintype "passive"))
      (node (ref "C17") (pin "2") (pinfunction "2_2") (pintype "passive"))
      (node (ref "C18") (pin "2") (pinfunction "2_2") (pintype "passive"))
      (node (ref "C19") (pin "2") (pinfunction "2_2") (pintype "passive"))
      (node (ref "C2") (pin "2") (pinfunction "2_2") (pintype "passive"))
      (node (ref "C20") (pin "2") (pinfunction "2_2") (pintype "passive"))
      (node (ref "C27") (pin "2") (pinfunction "2_2") (pintype "passive"))
      (node (ref "C3") (pin "2") (pinfunction "2_2") (pintype "passive"))
      (node (ref "C4") (pin "2") (pinfunction "2_2") (pintype "passive"))
      (node (ref "C41") (pin "2") (pinfunction "2_2") (pintype "passive"))
      (node (ref "C5") (pin "2") (pinfunction "2_2") (pintype "passive"))
      (node (ref "C6") (pin "2") (pinfunction "2_2") (pintype "passive"))
      (node (ref "C7") (pin "2") (pinfunction "2_2") (pintype "passive"))
      (node (ref "C71") (pin "2") (pinfunction "2_2") (pintype "passive"))
      (node (ref "C76") (pin "2") (pinfunction "2_2") (pintype "passive"))
      (node (ref "C77") (pin "2") (pinfunction "2_2") (pintype "passive"))
      (node (ref "C78") (pin "2") (pinfunction "2_2") (pintype "passive"))
      (node (ref "C8") (pin "2") (pinfunction "2_2") (pintype "passive"))
      (node (ref "C9") (pin "2") (pinfunction "2_2") (pintype "passive"))
      (node (ref "D1") (pin "1") (pinfunction "CLKIN_1") (pintype "bidirectional"))
      (node (ref "D1") (pin "11") (pinfunction "FSYNC_11") (pintype "bidirectional"))
      (node (ref "D1") (pin "18") (pinfunction "GND_18") (pintype "bidirectional"))
      (node (ref "D2") (pin "3") (pinfunction "GND_3") (pintype "power_in"))
      (node (ref "D3") (pin "12") (pinfunction "VSSA_12") (pintype "power_in"))
      (node (ref "D3") (pin "18") (pinfunction "VSS_4_18") (pintype "power_in"))
      (node (ref "D3") (pin "60") (pinfunction "BOOT0_60") (pintype "input"))
      (node (ref "D3") (pin "63") (pinfunction "VSS_3_63") (pintype "power_in"))
      (node (ref "D4") (pin "4") (pinfunction "GND_4") (pintype "power_in"))
      (node (ref "D5") (pin "2") (pinfunction "GND_2") (pintype "bidirectional"))
      (node (ref "D6") (pin "3") (pinfunction "GND_3") (pintype "bidirectional"))
      (node (ref "D6") (pin "4") (pinfunction "CSB1_4") (pintype "bidirectional"))
      (node (ref "D6") (pin "5") (pinfunction "CSB2_5") (pintype "bidirectional"))
      (node (ref "D7") (pin "11") (pinfunction "GND1_11") (pintype "bidirectional"))
      (node (ref "D7") (pin "9") (pinfunction "GND_9") (pintype "bidirectional"))
      (node (ref "D8") (pin "2") (pinfunction "GND_2") (pintype "bidirectional"))
      (node (ref "Q1") (pin "2") (pinfunction "GND_2") (pintype "power_in"))
      (node (ref "Q1") (pin "4") (pinfunction "GND_4") (pintype "power_in"))
      (node (ref "R12") (pin "1") (pinfunction "1_1") (pintype "passive"))
      (node (ref "R14") (pin "1") (pinfunction "1_1") (pintype "passive"))
      (node (ref "R19") (pin "1") (pinfunction "1_1") (pintype "passive"))
      (node (ref "R2") (pin "1") (pinfunction "1_1") (pintype "passive"))
      (node (ref "R9") (pin "1") (pinfunction "1_1") (pintype "passive"))
      (node (ref "S1") (pin "3") (pinfunction "P_3") (pintype "passive"))
      (node (ref "S1") (pin "4") (pinfunction "P_4") (pintype "passive"))
      (node (ref "V1") (pin "A") (pinfunction "A_A") (pintype "passive"))
      (node (ref "V8") (pin "2") (pinfunction "E_2") (pintype "passive"))
      (node (ref "X1") (pin "5") (pinfunction "GND_5") (pintype "passive"))
      (node (ref "X10") (pin "3") (pinfunction "1_3") (pintype "passive"))
      (node (ref "X11") (pin "1") (pinfunction "1_1") (pintype "passive"))
      (node (ref "X12") (pin "1") (pinfunction "1_1") (pintype "passive"))
      (node (ref "X13") (pin "1") (pinfunction "1_1") (pintype "passive"))
      (node (ref "X14") (pin "2") (pinfunction "1_2") (pintype "passive"))
      (node (ref "X15") (pin "1") (pinfunction "1_1") (pintype "passive"))
      (node (ref "X16") (pin "3") (pinfunction "1_3") (pintype "passive"))
      (node (ref "X17") (pin "1") (pinfunction "1_1") (pintype "passive"))
      (node (ref "X2") (pin "3") (pinfunction "1_3") (pintype "passive"))
      (node (ref "X20") (pin "3") (pinfunction "1_3") (pintype "passive"))
      (node (ref "X21") (pin "3") (pinfunction "1_3") (pintype "passive"))
      (node (ref "X22") (pin "3") (pinfunction "1_3") (pintype "passive"))
      (node (ref "X23") (pin "3") (pinfunction "1_3") (pintype "passive"))
      (node (ref "X24") (pin "3") (pinfunction "1_3") (pintype "passive"))
      (node (ref "X25") (pin "3") (pinfunction "1_3") (pintype "passive"))
      (node (ref "X26") (pin "3") (pinfunction "1_3") (pintype "passive"))
      (node (ref "X3") (pin "3") (pinfunction "1_3") (pintype "passive"))
      (node (ref "X4") (pin "3") (pinfunction "1_3") (pintype "passive"))
      (node (ref "X5") (pin "3") (pinfunction "1_3") (pintype "passive"))
      (node (ref "X6") (pin "3") (pinfunction "1_3") (pintype "passive"))
      (node (ref "X7") (pin "3") (pinfunction "1_3") (pintype "passive"))
      (node (ref "X8") (pin "3") (pinfunction "1_3") (pintype "passive"))
      (node (ref "X9") (pin "3") (pinfunction "1_3") (pintype "passive"))
    )
    (net (code "8") (name "INT_MPU6000") (class "Default")
      (node (ref "D1") (pin "12") (pinfunction "INT_12") (pintype "bidirectional"))
      (node (ref "D3") (pin "8") (pinfunction "PC0_8") (pintype "bidirectional"))
    )
    (net (code "9") (name "MISO") (class "Default")
      (node (ref "D3") (pin "10") (pinfunction "PC2_10") (pintype "bidirectional"))
      (node (ref "D4") (pin "2") (pinfunction "SO_2") (pintype "bidirectional"))
    )
    (net (code "10") (name "MISO2") (class "Default")
      (node (ref "D1") (pin "9") (pinfunction "AD0/SDO_9") (pintype "bidirectional"))
      (node (ref "D3") (pin "22") (pinfunction "PA6_22") (pintype "bidirectional"))
    )
    (net (code "11") (name "MOSI") (class "Default")
      (node (ref "D3") (pin "11") (pinfunction "PC3_11") (pintype "bidirectional"))
      (node (ref "D4") (pin "5") (pinfunction "SI_5") (pintype "input"))
    )
    (net (code "12") (name "MOSI2") (class "Default")
      (node (ref "D1") (pin "24") (pinfunction "SDA/SDI_24") (pintype "bidirectional"))
      (node (ref "D3") (pin "23") (pinfunction "PA7_23") (pintype "bidirectional"))
    )
    (net (code "13") (name "MPU6000") (class "Default")
      (node (ref "D1") (pin "8") (pinfunction "/CS_8") (pintype "bidirectional"))
      (node (ref "D3") (pin "24") (pinfunction "PC4_24") (pintype "bidirectional"))
    )
    (net (code "14") (name "Net-(C71-Pad1)") (class "Default")
      (node (ref "C71") (pin "1") (pinfunction "1_1") (pintype "passive"))
      (node (ref "Q1") (pin "1") (pinfunction "1_1") (pintype "passive"))
      (node (ref "R15") (pin "2") (pinfunction "2_2") (pintype "passive"))
    )
    (net (code "15") (name "Net-(D1-CPOUT)") (class "Default")
      (node (ref "C3") (pin "1") (pinfunction "1_1") (pintype "passive"))
      (node (ref "D1") (pin "20") (pinfunction "CPOUT_20") (pintype "bidirectional"))
    )
    (net (code "16") (name "Net-(D1-REGOUT)") (class "Default")
      (node (ref "C4") (pin "1") (pinfunction "1_1") (pintype "passive"))
      (node (ref "D1") (pin "10") (pinfunction "REGOUT_10") (pintype "bidirectional"))
    )
    (net (code "17") (name "Net-(D2A-I1)") (class "Default")
      (node (ref "D2") (pin "2") (pinfunction "I1_2") (pintype "input"))
      (node (ref "R12") (pin "2") (pinfunction "2_2") (pintype "passive"))
      (node (ref "X17") (pin "3") (pinfunction "1_3") (pintype "passive"))
    )
    (net (code "18") (name "Net-(D3A-VDDA)") (class "Default")
      (node (ref "C17") (pin "1") (pinfunction "1_1") (pintype "passive"))
      (node (ref "D3") (pin "13") (pinfunction "VDDA_13") (pintype "power_in"))
      (node (ref "L2") (pin "1") (pinfunction "1_1") (pintype "passive"))
    )
    (net (code "19") (name "Net-(D3F-PC13)") (class "Default")
      (node (ref "D3") (pin "2") (pinfunction "PC13_2") (pintype "bidirectional"))
      (node (ref "R8") (pin "2") (pinfunction "2_2") (pintype "passive"))
    )
    (net (code "20") (name "Net-(D3F-PC14)") (class "Default")
      (node (ref "D3") (pin "3") (pinfunction "PC14_3") (pintype "bidirectional"))
      (node (ref "R13") (pin "2") (pinfunction "2_2") (pintype "passive"))
    )
    (net (code "21") (name "Net-(D3H-PD0{slash}OSC<=)") (class "Default")
      (node (ref "C78") (pin "1") (pinfunction "1_1") (pintype "passive"))
      (node (ref "D3") (pin "5") (pinfunction "PD0/OSC<=_5") (pintype "bidirectional"))
      (node (ref "Q1") (pin "3") (pinfunction "2_3") (pintype "passive"))
    )
    (net (code "22") (name "Net-(D3H-PD1{slash}OSC=>)") (class "Default")
      (node (ref "D3") (pin "6") (pinfunction "PD1/OSC=>_6") (pintype "bidirectional"))
      (node (ref "R15") (pin "1") (pinfunction "1_1") (pintype "passive"))
    )
    (net (code "23") (name "Net-(D3I-VSS_1)") (class "Default")
      (node (ref "C77") (pin "1") (pinfunction "1_1") (pintype "passive"))
      (node (ref "D3") (pin "31") (pinfunction "VSS_1_31") (pintype "power_in"))
    )
    (net (code "24") (name "Net-(D3I-VSS_2)") (class "Default")
      (node (ref "C76") (pin "1") (pinfunction "1_1") (pintype "passive"))
      (node (ref "D3") (pin "47") (pinfunction "VSS_2_47") (pintype "power_in"))
    )
    (net (code "25") (name "Net-(D5-BYPASS)") (class "Default")
      (node (ref "C8") (pin "1") (pinfunction "1_1") (pintype "passive"))
      (node (ref "D5") (pin "4") (pinfunction "BYPASS_4") (pintype "bidirectional"))
    )
    (net (code "26") (name "Net-(D5-ON{slash}OFF)") (class "Default")
      (node (ref "C27") (pin "1") (pinfunction "1_1") (pintype "passive"))
      (node (ref "D5") (pin "1") (pinfunction "VIN_1") (pintype "bidirectional"))
      (node (ref "D5") (pin "3") (pinfunction "ON/OFF_3") (pintype "bidirectional"))
      (node (ref "V5") (pin "C") (pinfunction "C_C") (pintype "passive"))
      (node (ref "V7") (pin "C") (pinfunction "C_C") (pintype "passive"))
    )
    (net (code "27") (name "Net-(D7-C1)") (class "Default")
      (node (ref "C14") (pin "1") (pinfunction "1_1") (pintype "passive"))
      (node (ref "D7") (pin "10") (pinfunction "C1_10") (pintype "bidirectional"))
    )
    (net (code "28") (name "Net-(D7-SETC)") (class "Default")
      (node (ref "C16") (pin "2") (pinfunction "2_2") (pintype "passive"))
      (node (ref "D7") (pin "12") (pinfunction "SETC_12") (pintype "bidirectional"))
    )
    (net (code "29") (name "Net-(D7-SETP)") (class "Default")
      (node (ref "C16") (pin "1") (pinfunction "1_1") (pintype "passive"))
      (node (ref "D7") (pin "8") (pinfunction "SETP_8") (pintype "bidirectional"))
    )
    (net (code "30") (name "Net-(D8-BYPASS)") (class "Default")
      (node (ref "C20") (pin "1") (pinfunction "1_1") (pintype "passive"))
      (node (ref "D8") (pin "4") (pinfunction "BYPASS_4") (pintype "bidirectional"))
    )
    (net (code "31") (name "Net-(D8-ON{slash}OFF)") (class "Default")
      (node (ref "C18") (pin "1") (pinfunction "1_1") (pintype "passive"))
      (node (ref "D8") (pin "1") (pinfunction "VIN_1") (pintype "bidirectional"))
      (node (ref "D8") (pin "3") (pinfunction "ON/OFF_3") (pintype "bidirectional"))
      (node (ref "V3") (pin "C") (pinfunction "C_C") (pintype "passive"))
    )
    (net (code "32") (name "Net-(R3-Pad2)") (class "Default")
      (node (ref "R3") (pin "2") (pinfunction "2_2") (pintype "passive"))
      (node (ref "X14") (pin "1") (pinfunction "1_1") (pintype "passive"))
    )
    (net (code "33") (name "Net-(R8-Pad1)") (class "Default")
      (node (ref "R8") (pin "1") (pinfunction "1_1") (pintype "passive"))
      (node (ref "V4") (pin "C") (pinfunction "C_C") (pintype "passive"))
    )
    (net (code "34") (name "Net-(R9-Pad2)") (class "Default")
      (node (ref "R9") (pin "2") (pinfunction "2_2") (pintype "passive"))
      (node (ref "V6") (pin "C") (pinfunction "C_C") (pintype "passive"))
    )
    (net (code "35") (name "Net-(R13-Pad1)") (class "Default")
      (node (ref "R13") (pin "1") (pinfunction "1_1") (pintype "passive"))
      (node (ref "V2") (pin "C") (pinfunction "C_C") (pintype "passive"))
    )
    (net (code "36") (name "Net-(V8-B)") (class "Default")
      (node (ref "R11") (pin "2") (pinfunction "2_2") (pintype "passive"))
      (node (ref "V8") (pin "1") (pinfunction "B_1") (pintype "passive"))
    )
    (net (code "37") (name "Net-(V8-C)") (class "Default")
      (node (ref "V8") (pin "3") (pinfunction "C_3") (pintype "passive"))
      (node (ref "X18") (pin "2") (pinfunction "1_2") (pintype "passive"))
    )
    (net (code "38") (name "Net-(X1-D+)") (class "Default")
      (node (ref "R184") (pin "1") (pinfunction "1_1") (pintype "passive"))
      (node (ref "X1") (pin "3") (pinfunction "D+_3") (pintype "passive"))
    )
    (net (code "39") (name "Net-(X1-D-)") (class "Default")
      (node (ref "R185") (pin "1") (pinfunction "1_1") (pintype "passive"))
      (node (ref "X1") (pin "2") (pinfunction "D-_2") (pintype "passive"))
    )
    (net (code "40") (name "Net-(X2B-1)") (class "Default")
      (node (ref "SJ4") (pin "1") (pinfunction "1_1") (pintype "passive"))
      (node (ref "X2") (pin "2") (pinfunction "1_2") (pintype "passive"))
    )
    (net (code "41") (name "Net-(X3B-1)") (class "Default")
      (node (ref "SJ5") (pin "1") (pinfunction "1_1") (pintype "passive"))
      (node (ref "X3") (pin "2") (pinfunction "1_2") (pintype "passive"))
    )
    (net (code "42") (name "Net-(X4B-1)") (class "Default")
      (node (ref "SJ6") (pin "1") (pinfunction "1_1") (pintype "passive"))
      (node (ref "X4") (pin "2") (pinfunction "1_2") (pintype "passive"))
    )
    (net (code "43") (name "Net-(X5B-1)") (class "Default")
      (node (ref "SJ7") (pin "1") (pinfunction "1_1") (pintype "passive"))
      (node (ref "X5") (pin "2") (pinfunction "1_2") (pintype "passive"))
    )
    (net (code "44") (name "Net-(X6B-1)") (class "Default")
      (node (ref "SJ8") (pin "1") (pinfunction "1_1") (pintype "passive"))
      (node (ref "X6") (pin "2") (pinfunction "1_2") (pintype "passive"))
    )
    (net (code "45") (name "Net-(X7B-1)") (class "Default")
      (node (ref "SJ9") (pin "1") (pinfunction "1_1") (pintype "passive"))
      (node (ref "X7") (pin "2") (pinfunction "1_2") (pintype "passive"))
    )
    (net (code "46") (name "Net-(X8B-1)") (class "Default")
      (node (ref "SJ10") (pin "1") (pinfunction "1_1") (pintype "passive"))
      (node (ref "X8") (pin "2") (pinfunction "1_2") (pintype "passive"))
    )
    (net (code "47") (name "Net-(X9B-1)") (class "Default")
      (node (ref "SJ11") (pin "1") (pinfunction "1_1") (pintype "passive"))
      (node (ref "X9") (pin "2") (pinfunction "1_2") (pintype "passive"))
    )
    (net (code "48") (name "Net-(X10B-1)") (class "Default")
      (node (ref "SJ20") (pin "1") (pinfunction "1_1") (pintype "passive"))
      (node (ref "X10") (pin "2") (pinfunction "1_2") (pintype "passive"))
    )
    (net (code "49") (name "Net-(X11B-1)") (class "Default")
      (node (ref "SJ3") (pin "2") (pinfunction "2_2") (pintype "passive"))
      (node (ref "X11") (pin "2") (pinfunction "1_2") (pintype "passive"))
    )
    (net (code "50") (name "Net-(X12B-1)") (class "Default")
      (node (ref "SJ2") (pin "2") (pinfunction "2_2") (pintype "passive"))
      (node (ref "X12") (pin "2") (pinfunction "1_2") (pintype "passive"))
    )
    (net (code "51") (name "Net-(X13B-1)") (class "Default")
      (node (ref "SJ1") (pin "2") (pinfunction "2_2") (pintype "passive"))
      (node (ref "X13") (pin "2") (pinfunction "1_2") (pintype "passive"))
    )
    (net (code "52") (name "Net-(X15B-1)") (class "Default")
      (node (ref "SJ12") (pin "2") (pinfunction "2_2") (pintype "passive"))
      (node (ref "X15") (pin "2") (pinfunction "1_2") (pintype "passive"))
    )
    (net (code "53") (name "Net-(X17B-1)") (class "Default")
      (node (ref "SJ13") (pin "2") (pinfunction "2_2") (pintype "passive"))
      (node (ref "X17") (pin "2") (pinfunction "1_2") (pintype "passive"))
    )
    (net (code "54") (name "Net-(X20B-1)") (class "Default")
      (node (ref "SJ14") (pin "1") (pinfunction "1_1") (pintype "passive"))
      (node (ref "X20") (pin "2") (pinfunction "1_2") (pintype "passive"))
    )
    (net (code "55") (name "Net-(X21B-1)") (class "Default")
      (node (ref "SJ15") (pin "1") (pinfunction "1_1") (pintype "passive"))
      (node (ref "X21") (pin "2") (pinfunction "1_2") (pintype "passive"))
    )
    (net (code "56") (name "Net-(X22B-1)") (class "Default")
      (node (ref "SJ16") (pin "1") (pinfunction "1_1") (pintype "passive"))
      (node (ref "X22") (pin "2") (pinfunction "1_2") (pintype "passive"))
    )
    (net (code "57") (name "Net-(X23B-1)") (class "Default")
      (node (ref "SJ17") (pin "1") (pinfunction "1_1") (pintype "passive"))
      (node (ref "X23") (pin "2") (pinfunction "1_2") (pintype "passive"))
    )
    (net (code "58") (name "Net-(X24B-1)") (class "Default")
      (node (ref "SJ18") (pin "1") (pinfunction "1_1") (pintype "passive"))
      (node (ref "X24") (pin "2") (pinfunction "1_2") (pintype "passive"))
    )
    (net (code "59") (name "Net-(X25B-1)") (class "Default")
      (node (ref "SJ19") (pin "1") (pinfunction "1_1") (pintype "passive"))
      (node (ref "X25") (pin "2") (pinfunction "1_2") (pintype "passive"))
    )
    (net (code "60") (name "Net-(X26B-1)") (class "Default")
      (node (ref "SJ21") (pin "1") (pinfunction "1_1") (pintype "passive"))
      (node (ref "X26") (pin "2") (pinfunction "1_2") (pintype "passive"))
    )
    (net (code "61") (name "PMWIN4") (class "Default")
      (node (ref "D3") (pin "39") (pinfunction "PC8_39") (pintype "bidirectional"))
      (node (ref "X23") (pin "1") (pinfunction "1_1") (pintype "passive"))
    )
    (net (code "62") (name "PWM1") (class "Default")
      (node (ref "D3") (pin "56") (pinfunction "PB4_56") (pintype "bidirectional"))
      (node (ref "X2") (pin "1") (pinfunction "1_1") (pintype "passive"))
    )
    (net (code "63") (name "PWM2") (class "Default")
      (node (ref "D3") (pin "57") (pinfunction "PB5_57") (pintype "bidirectional"))
      (node (ref "X3") (pin "1") (pinfunction "1_1") (pintype "passive"))
    )
    (net (code "64") (name "PWM3") (class "Default")
      (node (ref "D3") (pin "26") (pinfunction "PB0_26") (pintype "bidirectional"))
      (node (ref "X4") (pin "1") (pinfunction "1_1") (pintype "passive"))
    )
    (net (code "65") (name "PWM4") (class "Default")
      (node (ref "D3") (pin "27") (pinfunction "PB1_27") (pintype "bidirectional"))
      (node (ref "X5") (pin "1") (pinfunction "1_1") (pintype "passive"))
    )
    (net (code "66") (name "PWM5") (class "Default")
      (node (ref "D3") (pin "35") (pinfunction "PB14_35") (pintype "bidirectional"))
      (node (ref "X6") (pin "1") (pinfunction "1_1") (pintype "passive"))
    )
    (net (code "67") (name "PWM6") (class "Default")
      (node (ref "D3") (pin "36") (pinfunction "PB15_36") (pintype "bidirectional"))
      (node (ref "X7") (pin "1") (pinfunction "1_1") (pintype "passive"))
    )
    (net (code "68") (name "PWM7") (class "Default")
      (node (ref "D3") (pin "61") (pinfunction "PB8_61") (pintype "bidirectional"))
      (node (ref "X8") (pin "1") (pinfunction "1_1") (pintype "passive"))
    )
    (net (code "69") (name "PWM8") (class "Default")
      (node (ref "D3") (pin "62") (pinfunction "PB9_62") (pintype "bidirectional"))
      (node (ref "X9") (pin "1") (pinfunction "1_1") (pintype "passive"))
    )
    (net (code "70") (name "PWMIN1") (class "Default")
      (node (ref "D3") (pin "43") (pinfunction "PA10_43") (pintype "bidirectional"))
      (node (ref "X20") (pin "1") (pinfunction "1_1") (pintype "passive"))
    )
    (net (code "71") (name "PWMIN2") (class "Default")
      (node (ref "D3") (pin "37") (pinfunction "PC6_37") (pintype "bidirectional"))
      (node (ref "X21") (pin "1") (pinfunction "1_1") (pintype "passive"))
    )
    (net (code "72") (name "PWMIN3") (class "Default")
      (node (ref "D3") (pin "38") (pinfunction "PC7_38") (pintype "bidirectional"))
      (node (ref "X22") (pin "1") (pinfunction "1_1") (pintype "passive"))
    )
    (net (code "73") (name "PWMIN5") (class "Default")
      (node (ref "D3") (pin "50") (pinfunction "PA15_50") (pintype "bidirectional"))
      (node (ref "X24") (pin "1") (pinfunction "1_1") (pintype "passive"))
    )
    (net (code "74") (name "PWMIN6") (class "Default")
      (node (ref "D3") (pin "55") (pinfunction "PB3_55") (pintype "bidirectional"))
      (node (ref "X25") (pin "1") (pinfunction "1_1") (pintype "passive"))
    )
    (net (code "75") (name "PWMIN7") (class "Default")
      (node (ref "D3") (pin "14") (pinfunction "PA0_14") (pintype "bidirectional"))
      (node (ref "X10") (pin "1") (pinfunction "1_1") (pintype "passive"))
    )
    (net (code "76") (name "PWMIN8") (class "Default")
      (node (ref "D3") (pin "15") (pinfunction "PA1_15") (pintype "bidirectional"))
      (node (ref "X26") (pin "1") (pinfunction "1_1") (pintype "passive"))
    )
    (net (code "77") (name "RX1") (class "Default")
      (node (ref "D3") (pin "59") (pinfunction "PB7_59") (pintype "bidirectional"))
      (node (ref "R5") (pin "1") (pinfunction "1_1") (pintype "passive"))
      (node (ref "X13") (pin "3") (pinfunction "1_3") (pintype "passive"))
    )
    (net (code "78") (name "RX2") (class "Default")
      (node (ref "D2") (pin "4") (pinfunction "O_4") (pintype "output"))
      (node (ref "D3") (pin "17") (pinfunction "PA3_17") (pintype "bidirectional"))
    )
    (net (code "79") (name "RX3") (class "Default")
      (node (ref "D3") (pin "30") (pinfunction "PB11_30") (pintype "bidirectional"))
      (node (ref "R7") (pin "1") (pinfunction "1_1") (pintype "passive"))
      (node (ref "X12") (pin "3") (pinfunction "1_3") (pintype "passive"))
    )
    (net (code "80") (name "RX4") (class "Default")
      (node (ref "D3") (pin "52") (pinfunction "PC11_52") (pintype "bidirectional"))
      (node (ref "X15") (pin "3") (pinfunction "1_3") (pintype "passive"))
    )
    (net (code "81") (name "RX5") (class "Default")
      (node (ref "D3") (pin "54") (pinfunction "PD2_54") (pintype "bidirectional"))
      (node (ref "X11") (pin "3") (pinfunction "1_3") (pintype "passive"))
    )
    (net (code "82") (name "SBUS") (class "Default")
      (node (ref "C7") (pin "1") (pinfunction "1_1") (pintype "passive"))
      (node (ref "D2") (pin "1") (pinfunction "I0_1") (pintype "input"))
      (node (ref "D3") (pin "28") (pinfunction "PB2_28") (pintype "bidirectional"))
      (node (ref "R14") (pin "2") (pinfunction "2_2") (pintype "passive"))
    )
    (net (code "83") (name "SCK") (class "Default")
      (node (ref "D3") (pin "34") (pinfunction "PB13_34") (pintype "bidirectional"))
      (node (ref "D4") (pin "6") (pinfunction "SCK_6") (pintype "input"))
    )
    (net (code "84") (name "SCK2") (class "Default")
      (node (ref "D1") (pin "23") (pinfunction "SCL/SCLK_23") (pintype "bidirectional"))
      (node (ref "D3") (pin "21") (pinfunction "PA5_21") (pintype "bidirectional"))
    )
    (net (code "85") (name "SCL") (class "Default")
      (node (ref "D3") (pin "41") (pinfunction "PA8_41") (pintype "bidirectional"))
      (node (ref "D6") (pin "8") (pinfunction "SCLK/SCL_8") (pintype "bidirectional"))
      (node (ref "D7") (pin "1") (pinfunction "SCL_1") (pintype "bidirectional"))
      (node (ref "R16") (pin "1") (pinfunction "1_1") (pintype "passive"))
    )
    (net (code "86") (name "SDA") (class "Default")
      (node (ref "D3") (pin "40") (pinfunction "PC9_40") (pintype "bidirectional"))
      (node (ref "D6") (pin "7") (pinfunction "SDI/SDA_7") (pintype "bidirectional"))
      (node (ref "D7") (pin "16") (pinfunction "SDA_16") (pintype "bidirectional"))
      (node (ref "R17") (pin "1") (pinfunction "1_1") (pintype "passive"))
    )
    (net (code "87") (name "SWCLK") (class "Default")
      (node (ref "D3") (pin "49") (pinfunction "PA14_49") (pintype "bidirectional"))
      (node (ref "X16") (pin "2") (pinfunction "1_2") (pintype "passive"))
    )
    (net (code "88") (name "SWDIO") (class "Default")
      (node (ref "D3") (pin "46") (pinfunction "PA13_46") (pintype "bidirectional"))
      (node (ref "X16") (pin "4") (pinfunction "1_4") (pintype "passive"))
    )
    (net (code "89") (name "TX1") (class "Default")
      (node (ref "D3") (pin "58") (pinfunction "PB6_58") (pintype "bidirectional"))
      (node (ref "R4") (pin "1") (pinfunction "1_1") (pintype "passive"))
      (node (ref "X13") (pin "4") (pinfunction "1_4") (pintype "passive"))
    )
    (net (code "90") (name "TX2") (class "Default")
      (node (ref "D3") (pin "16") (pinfunction "PA2_16") (pintype "bidirectional"))
      (node (ref "X17") (pin "4") (pinfunction "1_4") (pintype "passive"))
    )
    (net (code "91") (name "TX3") (class "Default")
      (node (ref "D3") (pin "29") (pinfunction "PB10_29") (pintype "bidirectional"))
      (node (ref "R6") (pin "1") (pinfunction "1_1") (pintype "passive"))
      (node (ref "X12") (pin "4") (pinfunction "1_4") (pintype "passive"))
    )
    (net (code "92") (name "TX4") (class "Default")
      (node (ref "D3") (pin "51") (pinfunction "PC10_51") (pintype "bidirectional"))
      (node (ref "X15") (pin "4") (pinfunction "1_4") (pintype "passive"))
    )
    (net (code "93") (name "TX5") (class "Default")
      (node (ref "D3") (pin "53") (pinfunction "PC12_53") (pintype "bidirectional"))
      (node (ref "X11") (pin "4") (pinfunction "1_4") (pintype "passive"))
    )
    (net (code "94") (name "USBDM") (class "Default")
      (node (ref "D3") (pin "44") (pinfunction "PA11_44") (pintype "bidirectional"))
      (node (ref "R185") (pin "2") (pinfunction "2_2") (pintype "passive"))
    )
    (net (code "95") (name "USBDP") (class "Default")
      (node (ref "D3") (pin "45") (pinfunction "PA12_45") (pintype "bidirectional"))
      (node (ref "R184") (pin "2") (pinfunction "2_2") (pintype "passive"))
    )
    (net (code "96") (name "VBUS") (class "Default")
      (node (ref "D3") (pin "42") (pinfunction "PA9_42") (pintype "bidirectional"))
      (node (ref "R1") (pin "1") (pinfunction "1_1") (pintype "passive"))
      (node (ref "R19") (pin "2") (pinfunction "2_2") (pintype "passive"))
    )
    (net (code "97") (name "VCC") (class "Default")
      (node (ref "C1") (pin "1") (pinfunction "1_1") (pintype "passive"))
      (node (ref "C10") (pin "1") (pinfunction "1_1") (pintype "passive"))
      (node (ref "C11") (pin "1") (pinfunction "1_1") (pintype "passive"))
      (node (ref "C13") (pin "1") (pinfunction "1_1") (pintype "passive"))
      (node (ref "C15") (pin "1") (pinfunction "1_1") (pintype "passive"))
      (node (ref "C2") (pin "1") (pinfunction "1_1") (pintype "passive"))
      (node (ref "C41") (pin "1") (pinfunction "1_1") (pintype "passive"))
      (node (ref "C5") (pin "1") (pinfunction "1_1") (pintype "passive"))
      (node (ref "C6") (pin "1") (pinfunction "1_1") (pintype "passive"))
      (node (ref "C9") (pin "1") (pinfunction "1_1") (pintype "passive"))
      (node (ref "D1") (pin "13") (pinfunction "VDD_13") (pintype "bidirectional"))
      (node (ref "D2") (pin "5") (pinfunction "VCC_5") (pintype "power_in"))
      (node (ref "D3") (pin "1") (pinfunction "VBAT_1") (pintype "power_in"))
      (node (ref "D3") (pin "19") (pinfunction "VDD_4_19") (pintype "power_in"))
      (node (ref "D3") (pin "32") (pinfunction "VDD_1_32") (pintype "power_in"))
      (node (ref "D3") (pin "48") (pinfunction "VDD_2_48") (pintype "power_in"))
      (node (ref "D3") (pin "64") (pinfunction "VDD_3_64") (pintype "power_in"))
      (node (ref "D4") (pin "3") (pinfunction "~{WP}_3") (pintype "input"))
      (node (ref "D4") (pin "7") (pinfunction "~{HOLD}_7") (pintype "input"))
      (node (ref "D4") (pin "8") (pinfunction "VCC_8") (pintype "power_in"))
      (node (ref "D5") (pin "5") (pinfunction "VOUT_5") (pintype "bidirectional"))
      (node (ref "D6") (pin "1") (pinfunction "VDD_1") (pintype "bidirectional"))
      (node (ref "D6") (pin "2") (pinfunction "PS_2") (pintype "bidirectional"))
      (node (ref "D7") (pin "13") (pinfunction "VDDIO_13") (pintype "bidirectional"))
      (node (ref "D7") (pin "2") (pinfunction "VDD_2") (pintype "bidirectional"))
      (node (ref "D7") (pin "4") (pinfunction "S1_4") (pintype "bidirectional"))
      (node (ref "L2") (pin "2") (pinfunction "2_2") (pintype "passive"))
      (node (ref "R10") (pin "2") (pinfunction "2_2") (pintype "passive"))
      (node (ref "R159") (pin "2") (pinfunction "2_2") (pintype "passive"))
      (node (ref "R16") (pin "2") (pinfunction "2_2") (pintype "passive"))
      (node (ref "R17") (pin "2") (pinfunction "2_2") (pintype "passive"))
      (node (ref "R4") (pin "2") (pinfunction "2_2") (pintype "passive"))
      (node (ref "R5") (pin "2") (pinfunction "2_2") (pintype "passive"))
      (node (ref "R6") (pin "2") (pinfunction "2_2") (pintype "passive"))
      (node (ref "R7") (pin "2") (pinfunction "2_2") (pintype "passive"))
      (node (ref "V2") (pin "A") (pinfunction "A_A") (pintype "passive"))
      (node (ref "V4") (pin "A") (pinfunction "A_A") (pintype "passive"))
      (node (ref "V6") (pin "A") (pinfunction "A_A") (pintype "passive"))
      (node (ref "X16") (pin "1") (pinfunction "1_1") (pintype "passive"))
    )
    (net (code "98") (name "VCCEXT") (class "Default")
      (node (ref "C19") (pin "1") (pinfunction "1_1") (pintype "passive"))
      (node (ref "D8") (pin "5") (pinfunction "VOUT_5") (pintype "bidirectional"))
      (node (ref "SJ1") (pin "1") (pinfunction "1_1") (pintype "passive"))
      (node (ref "SJ12") (pin "1") (pinfunction "1_1") (pintype "passive"))
      (node (ref "SJ13") (pin "1") (pinfunction "1_1") (pintype "passive"))
      (node (ref "SJ2") (pin "1") (pinfunction "1_1") (pintype "passive"))
      (node (ref "SJ3") (pin "1") (pinfunction "1_1") (pintype "passive"))
    )
    (net (code "99") (name "unconnected-(D1-AUX_CL-Pad7)") (class "Default")
      (node (ref "D1") (pin "7") (pinfunction "AUX_CL_7") (pintype "bidirectional"))
    )
    (net (code "100") (name "unconnected-(D1-AUX_DA-Pad6)") (class "Default")
      (node (ref "D1") (pin "6") (pinfunction "AUX_DA_6") (pintype "bidirectional"))
    )
    (net (code "101") (name "unconnected-(D1-CLKOUT-Pad22)") (class "Default")
      (node (ref "D1") (pin "22") (pinfunction "CLKOUT_22") (pintype "bidirectional"))
    )
    (net (code "102") (name "unconnected-(D3G-PC5-Pad25)") (class "Default")
      (node (ref "D3") (pin "25") (pinfunction "PC5_25") (pintype "bidirectional"))
    )
    (net (code "103") (name "unconnected-(D6-SDO-Pad6)") (class "Default")
      (node (ref "D6") (pin "6") (pinfunction "SDO_6") (pintype "bidirectional"))
    )
    (net (code "104") (name "unconnected-(X1-1-PadP$1)") (class "Default")
      (node (ref "X1") (pin "P$1") (pinfunction "1_P$1") (pintype "passive"))
    )
    (net (code "105") (name "unconnected-(X1-2-PadP$2)") (class "Default")
      (node (ref "X1") (pin "P$2") (pinfunction "2_P$2") (pintype "passive"))
    )
    (net (code "106") (name "unconnected-(X1-3-PadP$3)") (class "Default")
      (node (ref "X1") (pin "P$3") (pinfunction "3_P$3") (pintype "passive"))
    )
    (net (code "107") (name "unconnected-(X1-4-PadP$4)") (class "Default")
      (node (ref "X1") (pin "P$4") (pinfunction "4_P$4") (pintype "passive"))
    )
    (net (code "108") (name "unconnected-(X1-ID-Pad4)") (class "Default")
      (node (ref "X1") (pin "4") (pinfunction "ID_4") (pintype "passive"))
    )
    (net (code "109") (name "{slash}RESET") (class "Default")
      (node (ref "C12") (pin "1") (pinfunction "1_1") (pintype "passive"))
      (node (ref "D3") (pin "7") (pinfunction "NRST_7") (pintype "input"))
      (node (ref "R10") (pin "1") (pinfunction "1_1") (pintype "passive"))
      (node (ref "S1") (pin "1") (pinfunction "S_1") (pintype "passive"))
      (node (ref "S1") (pin "2") (pinfunction "S_2") (pintype "passive"))
    )
  )
)
